# PowerCell-vArsalan.net
KiCad netlist of a schematic drawn in EAGLE
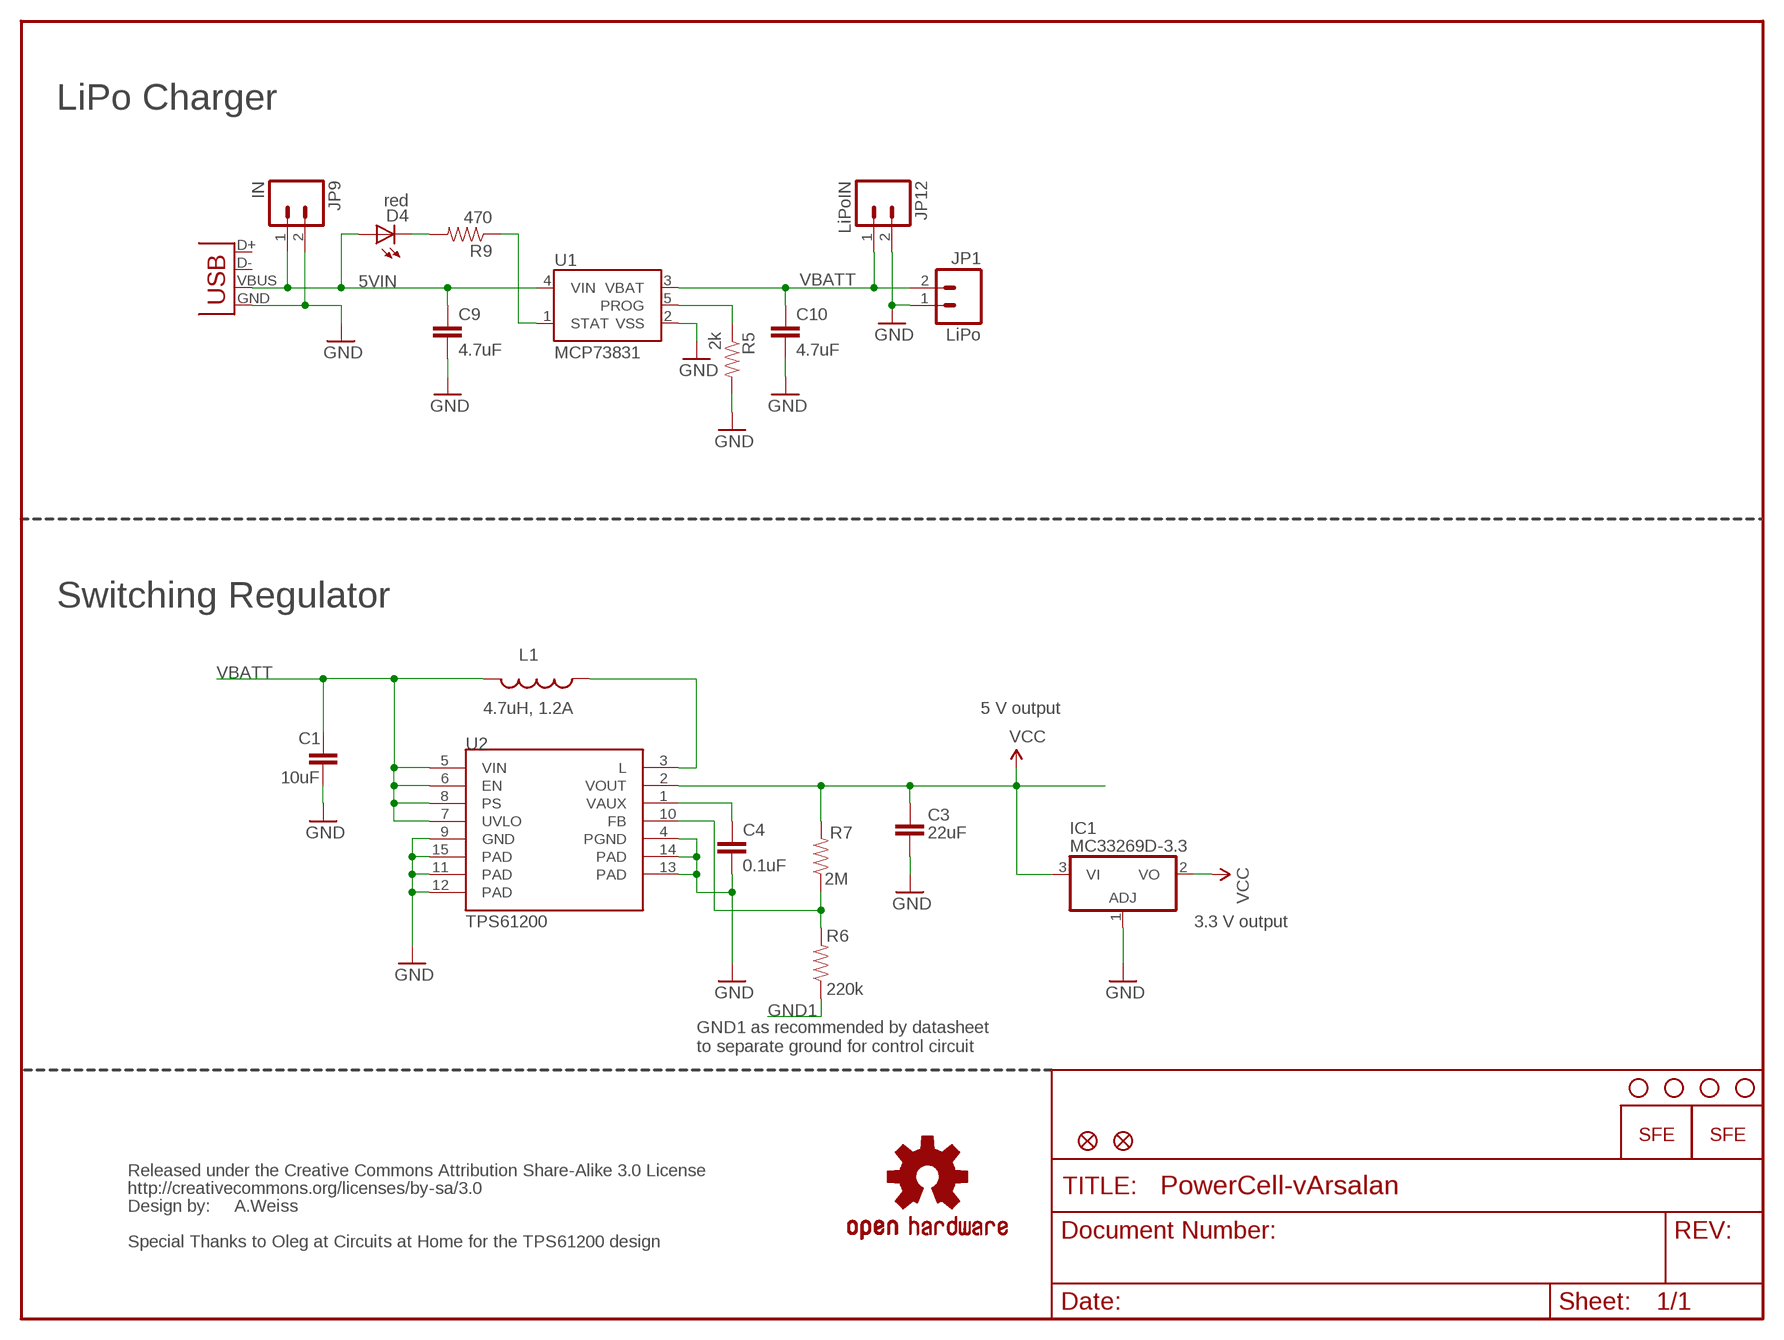
[diagram p0: schematic, sheet 1]

(export (version "E")
  (design (tool "Eeschema 10.0.6"))
  (components
    (comp (ref "C1")
      (value "10uF")
      (footprint "eagle-import:1206")
      (libsource (lib "eagle-import") (part "CAP1206"))
    )
    (comp (ref "C3")
      (value "22uF")
      (footprint "eagle-import:0805")
      (libsource (lib "eagle-import") (part "CAP0805"))
    )
    (comp (ref "C4")
      (value "0.1uF")
      (footprint "eagle-import:0402-CAP")
      (libsource (lib "eagle-import") (part "CAP0402-CAP"))
    )
    (comp (ref "C9")
      (value "4.7uF")
      (footprint "eagle-import:0402-CAP")
      (libsource (lib "eagle-import") (part "CAP0402-CAP"))
    )
    (comp (ref "C10")
      (value "4.7uF")
      (footprint "eagle-import:0402-CAP")
      (libsource (lib "eagle-import") (part "CAP0402-CAP"))
    )
    (comp (ref "D4")
      (value "red")
      (footprint "eagle-import:LED-0603")
      (libsource (lib "eagle-import") (part "LED0603"))
    )
    (comp (ref "IC1")
      (value "MC33269D-3.3")
      (footprint "eagle-import:DPACK")
      (libsource (lib "eagle-import") (part "MC33269?D-3.3"))
    )
    (comp (ref "JP1")
      (value "LiPo")
      (footprint "eagle-import:JST-2-SMD")
      (libsource (lib "eagle-import") (part "M02-JST-2MM-SMT"))
    )
    (comp (ref "JP3")
      (value "LOGO-SFENEW")
      (footprint "eagle-import:SFE-NEW-WEBLOGO")
      (libsource (lib "eagle-import") (part "LOGO-SFENEW"))
    )
    (comp (ref "JP4")
      (value "LOGO-SFESK")
      (footprint "eagle-import:SFE-LOGO-FLAME")
      (libsource (lib "eagle-import") (part "LOGO-SFESK"))
    )
    (comp (ref "JP5")
      (value "STAND-OFF")
      (footprint "eagle-import:STAND-OFF")
      (libsource (lib "eagle-import") (part "STAND-OFF"))
    )
    (comp (ref "JP6")
      (value "STAND-OFF")
      (footprint "eagle-import:STAND-OFF")
      (libsource (lib "eagle-import") (part "STAND-OFF"))
    )
    (comp (ref "JP7")
      (value "STAND-OFF")
      (footprint "eagle-import:STAND-OFF")
      (libsource (lib "eagle-import") (part "STAND-OFF"))
    )
    (comp (ref "JP8")
      (value "STAND-OFF")
      (footprint "eagle-import:STAND-OFF")
      (libsource (lib "eagle-import") (part "STAND-OFF"))
    )
    (comp (ref "JP9")
      (value "IN")
      (footprint "eagle-import:1X02")
      (libsource (lib "eagle-import") (part "M02PTH"))
    )
    (comp (ref "JP12")
      (value "LiPoIN")
      (footprint "eagle-import:1X02")
      (libsource (lib "eagle-import") (part "M02PTH"))
    )
    (comp (ref "JP15")
      (value "FIDUCIALUFIDUCIAL")
      (footprint "eagle-import:MICRO-FIDUCIAL")
      (libsource (lib "eagle-import") (part "FIDUCIALUFIDUCIAL"))
    )
    (comp (ref "JP16")
      (value "FIDUCIALUFIDUCIAL")
      (footprint "eagle-import:MICRO-FIDUCIAL")
      (libsource (lib "eagle-import") (part "FIDUCIALUFIDUCIAL"))
    )
    (comp (ref "L1")
      (value "4.7uH, 1.2A")
      (footprint "eagle-import:CDRH2D09")
      (libsource (lib "eagle-import") (part "INDUCTOR."))
    )
    (comp (ref "R5")
      (value "2k")
      (footprint "eagle-import:0402-RES")
      (libsource (lib "eagle-import") (part "RESISTOR0402-RES"))
    )
    (comp (ref "R6")
      (value "220k")
      (footprint "eagle-import:0402-RES")
      (libsource (lib "eagle-import") (part "RESISTOR0402-RES"))
    )
    (comp (ref "R7")
      (value "2M")
      (footprint "eagle-import:0402-RES")
      (libsource (lib "eagle-import") (part "RESISTOR0402-RES"))
    )
    (comp (ref "R9")
      (value "470")
      (footprint "eagle-import:0402-RES")
      (libsource (lib "eagle-import") (part "RESISTOR0402-RES"))
    )
    (comp (ref "U$1")
      (value "OSHW-LOGOS")
      (footprint "eagle-import:OSHW-LOGO-S")
      (libsource (lib "eagle-import") (part "OSHW-LOGOS"))
    )
    (comp (ref "U$2")
      (value "CREATIVE_COMMONS")
      (footprint "eagle-import:CREATIVE_COMMONS")
      (libsource (lib "eagle-import") (part "CREATIVE_COMMONS"))
    )
    (comp (ref "U1")
      (value "MCP73831")
      (footprint "eagle-import:SOT23-5")
      (libsource (lib "eagle-import") (part "MCP73831"))
    )
    (comp (ref "U2")
      (value "TPS61200")
      (footprint "eagle-import:QFN-10_PAD")
      (libsource (lib "eagle-import") (part "TPS61200"))
    )
    (comp (ref "X1")
      (value "USB-MICROB")
      (footprint "eagle-import:USB-MICROB")
      (libsource (lib "eagle-import") (part "USB-MICROB"))
    )
  )
  (nets
    (net (code "1") (name "/5VIN") (class "Default")
      (node (ref "C9") (pin "1") (pinfunction "1_1") (pintype "passive"))
      (node (ref "D4") (pin "A") (pinfunction "A_A") (pintype "passive"))
      (node (ref "JP9") (pin "1") (pinfunction "1_1") (pintype "passive"))
      (node (ref "U1") (pin "4") (pinfunction "VIN_4") (pintype "power_in"))
      (node (ref "X1") (pin "VBUS") (pinfunction "VBUS_VBUS") (pintype "bidirectional"))
    )
    (net (code "2") (name "/GND1") (class "Default")
      (node (ref "R6") (pin "1") (pinfunction "1_1") (pintype "passive"))
    )
    (net (code "3") (name "/VBATT") (class "Default")
      (node (ref "C1") (pin "1") (pinfunction "1_1") (pintype "passive"))
      (node (ref "C10") (pin "1") (pinfunction "1_1") (pintype "passive"))
      (node (ref "JP1") (pin "2") (pinfunction "2_2") (pintype "passive"))
      (node (ref "JP12") (pin "1") (pinfunction "1_1") (pintype "passive"))
      (node (ref "L1") (pin "P$2") (pinfunction "2_P$2") (pintype "passive"))
      (node (ref "U1") (pin "3") (pinfunction "VBAT_3") (pintype "power_in"))
      (node (ref "U2") (pin "5") (pinfunction "VIN_5") (pintype "power_in"))
      (node (ref "U2") (pin "6") (pinfunction "EN_6") (pintype "input"))
      (node (ref "U2") (pin "7") (pinfunction "UVLO_7") (pintype "passive"))
      (node (ref "U2") (pin "8") (pinfunction "PS_8") (pintype "input"))
    )
    (net (code "4") (name "GND") (class "Default")
      (node (ref "C1") (pin "2") (pinfunction "2_2") (pintype "passive"))
      (node (ref "C10") (pin "2") (pinfunction "2_2") (pintype "passive"))
      (node (ref "C3") (pin "2") (pinfunction "2_2") (pintype "passive"))
      (node (ref "C4") (pin "2") (pinfunction "2_2") (pintype "passive"))
      (node (ref "C9") (pin "2") (pinfunction "2_2") (pintype "passive"))
      (node (ref "IC1") (pin "1") (pinfunction "ADJ_1") (pintype "input"))
      (node (ref "JP1") (pin "1") (pinfunction "1_1") (pintype "passive"))
      (node (ref "JP12") (pin "2") (pinfunction "2_2") (pintype "passive"))
      (node (ref "JP9") (pin "2") (pinfunction "2_2") (pintype "passive"))
      (node (ref "R5") (pin "2") (pinfunction "2_2") (pintype "passive"))
      (node (ref "U1") (pin "2") (pinfunction "VSS_2") (pintype "power_in"))
      (node (ref "U2") (pin "11") (pinfunction "PAD_11") (pintype "power_in"))
      (node (ref "U2") (pin "12") (pinfunction "PAD_12") (pintype "power_in"))
      (node (ref "U2") (pin "13") (pinfunction "PAD_13") (pintype "power_in"))
      (node (ref "U2") (pin "14") (pinfunction "PAD_14") (pintype "power_in"))
      (node (ref "U2") (pin "15") (pinfunction "PAD_15") (pintype "power_in"))
      (node (ref "U2") (pin "4") (pinfunction "PGND_4") (pintype "power_in"))
      (node (ref "U2") (pin "9") (pinfunction "GND_9") (pintype "power_in"))
      (node (ref "X1") (pin "GND") (pinfunction "GND_GND") (pintype "bidirectional"))
    )
    (net (code "5") (name "Net-(D4-PadC)") (class "Default")
      (node (ref "D4") (pin "C") (pinfunction "C_C") (pintype "passive"))
      (node (ref "R9") (pin "2") (pinfunction "2_2") (pintype "passive"))
    )
    (net (code "6") (name "Net-(L1-1)") (class "Default")
      (node (ref "L1") (pin "P$1") (pinfunction "1_P$1") (pintype "passive"))
      (node (ref "U2") (pin "3") (pinfunction "L_3") (pintype "passive"))
    )
    (net (code "7") (name "Net-(U1-PROG)") (class "Default")
      (node (ref "R5") (pin "1") (pinfunction "1_1") (pintype "passive"))
      (node (ref "U1") (pin "5") (pinfunction "PROG_5") (pintype "input"))
    )
    (net (code "8") (name "Net-(U1-STAT)") (class "Default")
      (node (ref "R9") (pin "1") (pinfunction "1_1") (pintype "passive"))
      (node (ref "U1") (pin "1") (pinfunction "STAT_1") (pintype "output"))
    )
    (net (code "9") (name "Net-(U2-FB)") (class "Default")
      (node (ref "R6") (pin "2") (pinfunction "2_2") (pintype "passive"))
      (node (ref "R7") (pin "1") (pinfunction "1_1") (pintype "passive"))
      (node (ref "U2") (pin "10") (pinfunction "FB_10") (pintype "passive"))
    )
    (net (code "10") (name "Net-(U2-VAUX)") (class "Default")
      (node (ref "C4") (pin "1") (pinfunction "1_1") (pintype "passive"))
      (node (ref "U2") (pin "1") (pinfunction "VAUX_1") (pintype "passive"))
    )
    (net (code "11") (name "VCC") (class "Default")
      (node (ref "C3") (pin "1") (pinfunction "1_1") (pintype "passive"))
      (node (ref "IC1") (pin "2") (pinfunction "VO_2") (pintype "passive"))
      (node (ref "IC1") (pin "3") (pinfunction "VI_3") (pintype "input"))
      (node (ref "R7") (pin "2") (pinfunction "2_2") (pintype "passive"))
      (node (ref "U2") (pin "2") (pinfunction "VOUT_2") (pintype "passive"))
    )
    (net (code "12") (name "unconnected-(X1-PadD+)") (class "Default")
      (node (ref "X1") (pin "D+") (pinfunction "D+_D+") (pintype "bidirectional"))
    )
    (net (code "13") (name "unconnected-(X1-PadD-)") (class "Default")
      (node (ref "X1") (pin "D-") (pinfunction "D-_D-") (pintype "bidirectional"))
    )
  )
)
